# xvim-001.net
KiCad netlist of a schematic drawn in EAGLE
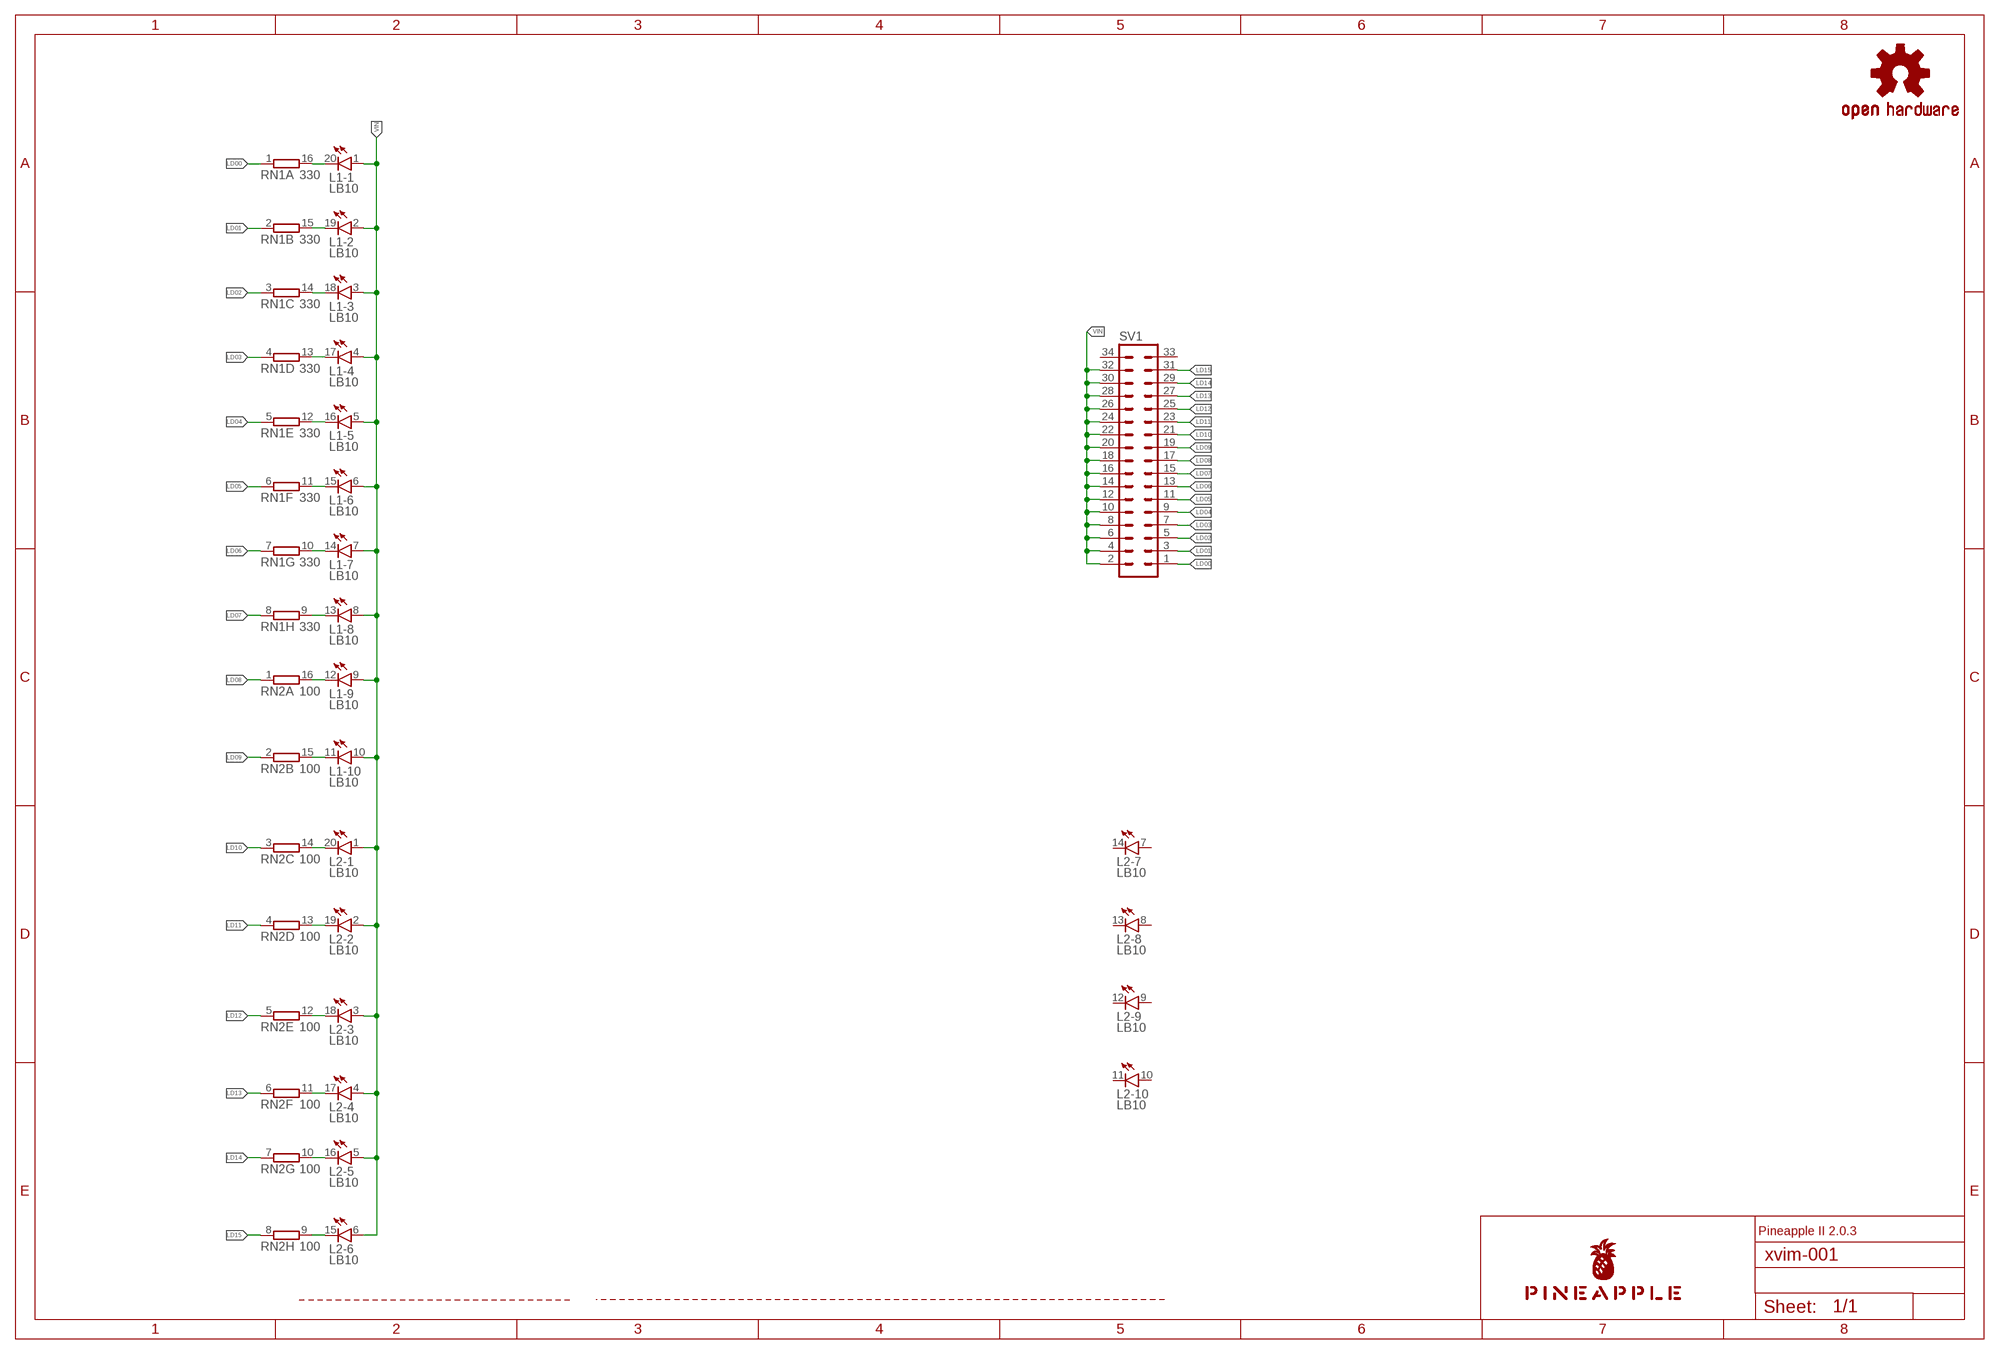
[diagram p0: schematic, sheet 1]

(export (version "E")
  (design (tool "Eeschema 10.0.6"))
  (components
    (comp (ref "L1")
      (value "LB10")
      (footprint "eagle-import:LB10")
      (libsource (lib "eagle-import") (part "LB10"))
    )
    (comp (ref "L2")
      (value "LB10")
      (footprint "eagle-import:LB10")
      (libsource (lib "eagle-import") (part "LB10"))
    )
    (comp (ref "LOGO1")
      (value "OSHW-LOGOS-COPPER")
      (footprint "eagle-import:OSHW-LOGO-S_COPPER")
      (libsource (lib "eagle-import") (part "OSHW-LOGOS-COPPER"))
    )
    (comp (ref "RN1")
      (value "330")
      (footprint "eagle-import:DIL16")
      (libsource (lib "eagle-import") (part "8R-N"))
    )
    (comp (ref "RN2")
      (value "100")
      (footprint "eagle-import:DIL16")
      (libsource (lib "eagle-import") (part "8R-N"))
    )
    (comp (ref "SV1")
      (value "ML34L")
      (footprint "eagle-import:ML34L")
      (libsource (lib "eagle-import") (part "ML34L"))
    )
    (comp (ref "U$1")
      (value "PINEAPPLE450_SILK")
      (footprint "eagle-import:PINEAPPLE450_SILK")
      (libsource (lib "eagle-import") (part "PINEAPPLE450_SILK"))
    )
  )
  (nets
    (net (code "1") (name "LD00") (class "Default")
      (node (ref "RN1") (pin "1") (pinfunction "1_1") (pintype "passive"))
      (node (ref "SV1") (pin "1") (pinfunction "1_1") (pintype "passive"))
    )
    (net (code "2") (name "LD01") (class "Default")
      (node (ref "RN1") (pin "2") (pinfunction "1_2") (pintype "passive"))
      (node (ref "SV1") (pin "3") (pinfunction "3_3") (pintype "passive"))
    )
    (net (code "3") (name "LD02") (class "Default")
      (node (ref "RN1") (pin "3") (pinfunction "1_3") (pintype "passive"))
      (node (ref "SV1") (pin "5") (pinfunction "5_5") (pintype "passive"))
    )
    (net (code "4") (name "LD03") (class "Default")
      (node (ref "RN1") (pin "4") (pinfunction "1_4") (pintype "passive"))
      (node (ref "SV1") (pin "7") (pinfunction "7_7") (pintype "passive"))
    )
    (net (code "5") (name "LD04") (class "Default")
      (node (ref "RN1") (pin "5") (pinfunction "1_5") (pintype "passive"))
      (node (ref "SV1") (pin "9") (pinfunction "9_9") (pintype "passive"))
    )
    (net (code "6") (name "LD05") (class "Default")
      (node (ref "RN1") (pin "6") (pinfunction "1_6") (pintype "passive"))
      (node (ref "SV1") (pin "11") (pinfunction "11_11") (pintype "passive"))
    )
    (net (code "7") (name "LD06") (class "Default")
      (node (ref "RN1") (pin "7") (pinfunction "1_7") (pintype "passive"))
      (node (ref "SV1") (pin "13") (pinfunction "13_13") (pintype "passive"))
    )
    (net (code "8") (name "LD07") (class "Default")
      (node (ref "RN1") (pin "8") (pinfunction "1_8") (pintype "passive"))
      (node (ref "SV1") (pin "15") (pinfunction "15_15") (pintype "passive"))
    )
    (net (code "9") (name "LD08") (class "Default")
      (node (ref "RN2") (pin "1") (pinfunction "1_1") (pintype "passive"))
      (node (ref "SV1") (pin "17") (pinfunction "17_17") (pintype "passive"))
    )
    (net (code "10") (name "LD09") (class "Default")
      (node (ref "RN2") (pin "2") (pinfunction "1_2") (pintype "passive"))
      (node (ref "SV1") (pin "19") (pinfunction "19_19") (pintype "passive"))
    )
    (net (code "11") (name "LD10") (class "Default")
      (node (ref "RN2") (pin "3") (pinfunction "1_3") (pintype "passive"))
      (node (ref "SV1") (pin "21") (pinfunction "21_21") (pintype "passive"))
    )
    (net (code "12") (name "LD11") (class "Default")
      (node (ref "RN2") (pin "4") (pinfunction "1_4") (pintype "passive"))
      (node (ref "SV1") (pin "23") (pinfunction "23_23") (pintype "passive"))
    )
    (net (code "13") (name "LD12") (class "Default")
      (node (ref "RN2") (pin "5") (pinfunction "1_5") (pintype "passive"))
      (node (ref "SV1") (pin "25") (pinfunction "25_25") (pintype "passive"))
    )
    (net (code "14") (name "LD13") (class "Default")
      (node (ref "RN2") (pin "6") (pinfunction "1_6") (pintype "passive"))
      (node (ref "SV1") (pin "27") (pinfunction "27_27") (pintype "passive"))
    )
    (net (code "15") (name "LD14") (class "Default")
      (node (ref "RN2") (pin "7") (pinfunction "1_7") (pintype "passive"))
      (node (ref "SV1") (pin "29") (pinfunction "29_29") (pintype "passive"))
    )
    (net (code "16") (name "LD15") (class "Default")
      (node (ref "RN2") (pin "8") (pinfunction "1_8") (pintype "passive"))
      (node (ref "SV1") (pin "31") (pinfunction "31_31") (pintype "passive"))
    )
    (net (code "17") (name "Net-(L1A-C)") (class "Default")
      (node (ref "L1") (pin "20") (pinfunction "C_20") (pintype "passive"))
      (node (ref "RN1") (pin "16") (pinfunction "2_16") (pintype "passive"))
    )
    (net (code "18") (name "Net-(L1B-C)") (class "Default")
      (node (ref "L1") (pin "11") (pinfunction "C_11") (pintype "passive"))
      (node (ref "RN2") (pin "15") (pinfunction "2_15") (pintype "passive"))
    )
    (net (code "19") (name "Net-(L1C-C)") (class "Default")
      (node (ref "L1") (pin "19") (pinfunction "C_19") (pintype "passive"))
      (node (ref "RN1") (pin "15") (pinfunction "2_15") (pintype "passive"))
    )
    (net (code "20") (name "Net-(L1D-C)") (class "Default")
      (node (ref "L1") (pin "18") (pinfunction "C_18") (pintype "passive"))
      (node (ref "RN1") (pin "14") (pinfunction "2_14") (pintype "passive"))
    )
    (net (code "21") (name "Net-(L1E-C)") (class "Default")
      (node (ref "L1") (pin "17") (pinfunction "C_17") (pintype "passive"))
      (node (ref "RN1") (pin "13") (pinfunction "2_13") (pintype "passive"))
    )
    (net (code "22") (name "Net-(L1F-C)") (class "Default")
      (node (ref "L1") (pin "16") (pinfunction "C_16") (pintype "passive"))
      (node (ref "RN1") (pin "12") (pinfunction "2_12") (pintype "passive"))
    )
    (net (code "23") (name "Net-(L1G-C)") (class "Default")
      (node (ref "L1") (pin "15") (pinfunction "C_15") (pintype "passive"))
      (node (ref "RN1") (pin "11") (pinfunction "2_11") (pintype "passive"))
    )
    (net (code "24") (name "Net-(L1H-C)") (class "Default")
      (node (ref "L1") (pin "14") (pinfunction "C_14") (pintype "passive"))
      (node (ref "RN1") (pin "10") (pinfunction "2_10") (pintype "passive"))
    )
    (net (code "25") (name "Net-(L1I-C)") (class "Default")
      (node (ref "L1") (pin "13") (pinfunction "C_13") (pintype "passive"))
      (node (ref "RN1") (pin "9") (pinfunction "2_9") (pintype "passive"))
    )
    (net (code "26") (name "Net-(L1J-C)") (class "Default")
      (node (ref "L1") (pin "12") (pinfunction "C_12") (pintype "passive"))
      (node (ref "RN2") (pin "16") (pinfunction "2_16") (pintype "passive"))
    )
    (net (code "27") (name "Net-(L2A-C)") (class "Default")
      (node (ref "L2") (pin "20") (pinfunction "C_20") (pintype "passive"))
      (node (ref "RN2") (pin "14") (pinfunction "2_14") (pintype "passive"))
    )
    (net (code "28") (name "Net-(L2C-C)") (class "Default")
      (node (ref "L2") (pin "19") (pinfunction "C_19") (pintype "passive"))
      (node (ref "RN2") (pin "13") (pinfunction "2_13") (pintype "passive"))
    )
    (net (code "29") (name "Net-(L2D-C)") (class "Default")
      (node (ref "L2") (pin "18") (pinfunction "C_18") (pintype "passive"))
      (node (ref "RN2") (pin "12") (pinfunction "2_12") (pintype "passive"))
    )
    (net (code "30") (name "Net-(L2E-C)") (class "Default")
      (node (ref "L2") (pin "17") (pinfunction "C_17") (pintype "passive"))
      (node (ref "RN2") (pin "11") (pinfunction "2_11") (pintype "passive"))
    )
    (net (code "31") (name "Net-(L2F-C)") (class "Default")
      (node (ref "L2") (pin "16") (pinfunction "C_16") (pintype "passive"))
      (node (ref "RN2") (pin "10") (pinfunction "2_10") (pintype "passive"))
    )
    (net (code "32") (name "Net-(L2G-C)") (class "Default")
      (node (ref "L2") (pin "15") (pinfunction "C_15") (pintype "passive"))
      (node (ref "RN2") (pin "9") (pinfunction "2_9") (pintype "passive"))
    )
    (net (code "33") (name "VIN") (class "Default")
      (node (ref "L1") (pin "1") (pinfunction "A_1") (pintype "passive"))
      (node (ref "L1") (pin "10") (pinfunction "A_10") (pintype "passive"))
      (node (ref "L1") (pin "2") (pinfunction "A_2") (pintype "passive"))
      (node (ref "L1") (pin "3") (pinfunction "A_3") (pintype "passive"))
      (node (ref "L1") (pin "4") (pinfunction "A_4") (pintype "passive"))
      (node (ref "L1") (pin "5") (pinfunction "A_5") (pintype "passive"))
      (node (ref "L1") (pin "6") (pinfunction "A_6") (pintype "passive"))
      (node (ref "L1") (pin "7") (pinfunction "A_7") (pintype "passive"))
      (node (ref "L1") (pin "8") (pinfunction "A_8") (pintype "passive"))
      (node (ref "L1") (pin "9") (pinfunction "A_9") (pintype "passive"))
      (node (ref "L2") (pin "1") (pinfunction "A_1") (pintype "passive"))
      (node (ref "L2") (pin "2") (pinfunction "A_2") (pintype "passive"))
      (node (ref "L2") (pin "3") (pinfunction "A_3") (pintype "passive"))
      (node (ref "L2") (pin "4") (pinfunction "A_4") (pintype "passive"))
      (node (ref "L2") (pin "5") (pinfunction "A_5") (pintype "passive"))
      (node (ref "L2") (pin "6") (pinfunction "A_6") (pintype "passive"))
      (node (ref "SV1") (pin "10") (pinfunction "10_10") (pintype "passive"))
      (node (ref "SV1") (pin "12") (pinfunction "12_12") (pintype "passive"))
      (node (ref "SV1") (pin "14") (pinfunction "14_14") (pintype "passive"))
      (node (ref "SV1") (pin "16") (pinfunction "16_16") (pintype "passive"))
      (node (ref "SV1") (pin "18") (pinfunction "18_18") (pintype "passive"))
      (node (ref "SV1") (pin "2") (pinfunction "2_2") (pintype "passive"))
      (node (ref "SV1") (pin "20") (pinfunction "20_20") (pintype "passive"))
      (node (ref "SV1") (pin "22") (pinfunction "22_22") (pintype "passive"))
      (node (ref "SV1") (pin "24") (pinfunction "24_24") (pintype "passive"))
      (node (ref "SV1") (pin "26") (pinfunction "26_26") (pintype "passive"))
      (node (ref "SV1") (pin "28") (pinfunction "28_28") (pintype "passive"))
      (node (ref "SV1") (pin "30") (pinfunction "30_30") (pintype "passive"))
      (node (ref "SV1") (pin "32") (pinfunction "32_32") (pintype "passive"))
      (node (ref "SV1") (pin "4") (pinfunction "4_4") (pintype "passive"))
      (node (ref "SV1") (pin "6") (pinfunction "6_6") (pintype "passive"))
      (node (ref "SV1") (pin "8") (pinfunction "8_8") (pintype "passive"))
    )
    (net (code "34") (name "unconnected-(L2B-A-Pad10)") (class "Default")
      (node (ref "L2") (pin "10") (pinfunction "A_10") (pintype "passive"))
    )
    (net (code "35") (name "unconnected-(L2B-C-Pad11)") (class "Default")
      (node (ref "L2") (pin "11") (pinfunction "C_11") (pintype "passive"))
    )
    (net (code "36") (name "unconnected-(L2H-A-Pad7)") (class "Default")
      (node (ref "L2") (pin "7") (pinfunction "A_7") (pintype "passive"))
    )
    (net (code "37") (name "unconnected-(L2H-C-Pad14)") (class "Default")
      (node (ref "L2") (pin "14") (pinfunction "C_14") (pintype "passive"))
    )
    (net (code "38") (name "unconnected-(L2I-A-Pad8)") (class "Default")
      (node (ref "L2") (pin "8") (pinfunction "A_8") (pintype "passive"))
    )
    (net (code "39") (name "unconnected-(L2I-C-Pad13)") (class "Default")
      (node (ref "L2") (pin "13") (pinfunction "C_13") (pintype "passive"))
    )
    (net (code "40") (name "unconnected-(L2J-A-Pad9)") (class "Default")
      (node (ref "L2") (pin "9") (pinfunction "A_9") (pintype "passive"))
    )
    (net (code "41") (name "unconnected-(L2J-C-Pad12)") (class "Default")
      (node (ref "L2") (pin "12") (pinfunction "C_12") (pintype "passive"))
    )
    (net (code "42") (name "unconnected-(SV1-Pad33)") (class "Default")
      (node (ref "SV1") (pin "33") (pinfunction "33_33") (pintype "passive"))
    )
    (net (code "43") (name "unconnected-(SV1-Pad34)") (class "Default")
      (node (ref "SV1") (pin "34") (pinfunction "34_34") (pintype "passive"))
    )
  )
)
